# HBridge.net
KiCad netlist of a schematic drawn in EAGLE
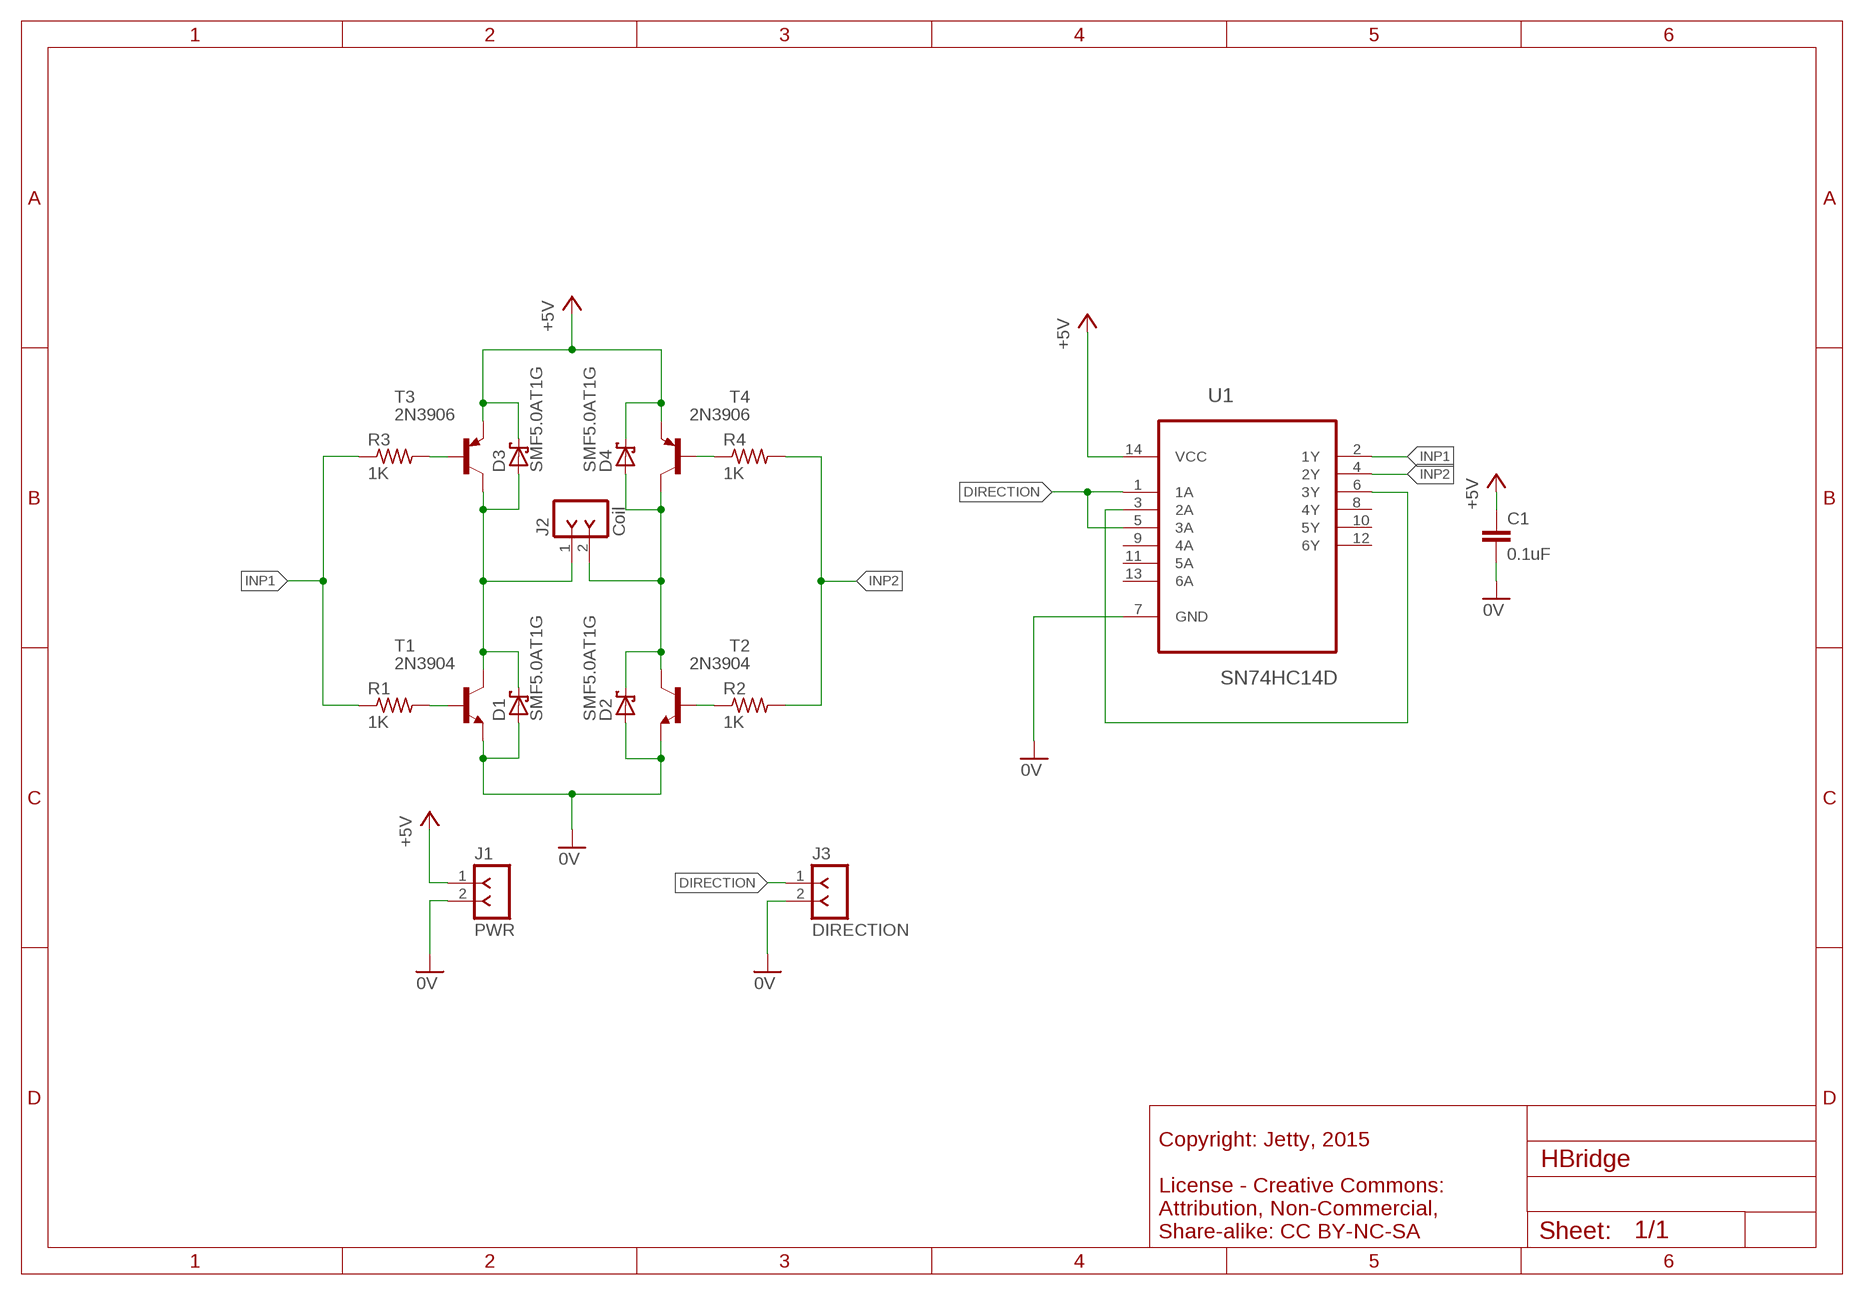
[diagram p0: schematic, sheet 1]

(export (version "E")
  (design (tool "Eeschema 10.0.6"))
  (components
    (comp (ref "C1")
      (value "0.1uF")
      (footprint "eagle-import:C0603")
      (libsource (lib "eagle-import") (part "C-EUC0603"))
    )
    (comp (ref "D1")
      (value "SMF5.0AT1G")
      (footprint "eagle-import:SOD123FL")
      (libsource (lib "eagle-import") (part "SMF5.0AT1"))
    )
    (comp (ref "D2")
      (value "SMF5.0AT1G")
      (footprint "eagle-import:SOD123FL")
      (libsource (lib "eagle-import") (part "SMF5.0AT1"))
    )
    (comp (ref "D3")
      (value "SMF5.0AT1G")
      (footprint "eagle-import:SOD123FL")
      (libsource (lib "eagle-import") (part "SMF5.0AT1"))
    )
    (comp (ref "D4")
      (value "SMF5.0AT1G")
      (footprint "eagle-import:SOD123FL")
      (libsource (lib "eagle-import") (part "SMF5.0AT1"))
    )
    (comp (ref "J1")
      (value "PWR")
      (footprint "eagle-import:SIP-100-02-32Y")
      (libsource (lib "eagle-import") (part "F-1X02-SIP-100-32Y"))
    )
    (comp (ref "J2")
      (value "Coil")
      (footprint "eagle-import:SIP-100-02-32Y")
      (libsource (lib "eagle-import") (part "F-1X02-SIP-100-32Y"))
    )
    (comp (ref "J3")
      (value "DIRECTION")
      (footprint "eagle-import:SIP-100-02-32Y")
      (libsource (lib "eagle-import") (part "F-1X02-SIP-100-32Y"))
    )
    (comp (ref "R1")
      (value "1K")
      (footprint "eagle-import:R0603")
      (libsource (lib "eagle-import") (part "R-US_R0603"))
    )
    (comp (ref "R2")
      (value "1K")
      (footprint "eagle-import:R0603")
      (libsource (lib "eagle-import") (part "R-US_R0603"))
    )
    (comp (ref "R3")
      (value "1K")
      (footprint "eagle-import:R0603")
      (libsource (lib "eagle-import") (part "R-US_R0603"))
    )
    (comp (ref "R4")
      (value "1K")
      (footprint "eagle-import:R0603")
      (libsource (lib "eagle-import") (part "R-US_R0603"))
    )
    (comp (ref "T1")
      (value "2N3904")
      (footprint "eagle-import:SOT23-BEC")
      (libsource (lib "eagle-import") (part "-NPN-SOT23-BECMMBT3904LT1"))
    )
    (comp (ref "T2")
      (value "2N3904")
      (footprint "eagle-import:SOT23-BEC")
      (libsource (lib "eagle-import") (part "-NPN-SOT23-BECMMBT3904LT1"))
    )
    (comp (ref "T3")
      (value "2N3906")
      (footprint "eagle-import:SOT23-BEC")
      (libsource (lib "eagle-import") (part "-PNP-SOT23-BECMMBT3906LT1"))
    )
    (comp (ref "T4")
      (value "2N3906")
      (footprint "eagle-import:SOT23-BEC")
      (libsource (lib "eagle-import") (part "-PNP-SOT23-BECMMBT3906LT1"))
    )
    (comp (ref "U1")
      (value "SN74HC14D")
      (footprint "eagle-import:SOIC127P600X175-14N")
      (libsource (lib "eagle-import") (part "SN74HC14D"))
    )
  )
  (nets
    (net (code "1") (name "+5V") (class "Default")
      (node (ref "C1") (pin "1") (pinfunction "1_1") (pintype "passive"))
      (node (ref "D3") (pin "C") (pinfunction "C_C") (pintype "passive"))
      (node (ref "D4") (pin "C") (pinfunction "C_C") (pintype "passive"))
      (node (ref "J1") (pin "1") (pinfunction "1_1") (pintype "passive"))
      (node (ref "T3") (pin "E") (pinfunction "E_E") (pintype "passive"))
      (node (ref "T4") (pin "E") (pinfunction "E_E") (pintype "passive"))
      (node (ref "U1") (pin "14") (pinfunction "VCC_14") (pintype "power_in"))
    )
    (net (code "2") (name "0V") (class "Default")
      (node (ref "C1") (pin "2") (pinfunction "2_2") (pintype "passive"))
      (node (ref "D1") (pin "A") (pinfunction "A_A") (pintype "passive"))
      (node (ref "D2") (pin "A") (pinfunction "A_A") (pintype "passive"))
      (node (ref "J1") (pin "2") (pinfunction "2_2") (pintype "passive"))
      (node (ref "J3") (pin "2") (pinfunction "2_2") (pintype "passive"))
      (node (ref "T1") (pin "E") (pinfunction "E_E") (pintype "passive"))
      (node (ref "T2") (pin "E") (pinfunction "E_E") (pintype "passive"))
      (node (ref "U1") (pin "7") (pinfunction "GND_7") (pintype "passive"))
    )
    (net (code "3") (name "DIRECTION") (class "Default")
      (node (ref "J3") (pin "1") (pinfunction "1_1") (pintype "passive"))
      (node (ref "U1") (pin "1") (pinfunction "1A_1") (pintype "input"))
      (node (ref "U1") (pin "5") (pinfunction "3A_5") (pintype "input"))
    )
    (net (code "4") (name "INP1") (class "Default")
      (node (ref "R1") (pin "1") (pinfunction "1_1") (pintype "passive"))
      (node (ref "R3") (pin "1") (pinfunction "1_1") (pintype "passive"))
      (node (ref "U1") (pin "2") (pinfunction "1Y_2") (pintype "output"))
    )
    (net (code "5") (name "INP2") (class "Default")
      (node (ref "R2") (pin "2") (pinfunction "2_2") (pintype "passive"))
      (node (ref "R4") (pin "2") (pinfunction "2_2") (pintype "passive"))
      (node (ref "U1") (pin "4") (pinfunction "2Y_4") (pintype "output"))
    )
    (net (code "6") (name "Net-(D1-PadC)") (class "Default")
      (node (ref "D1") (pin "C") (pinfunction "C_C") (pintype "passive"))
      (node (ref "D3") (pin "A") (pinfunction "A_A") (pintype "passive"))
      (node (ref "J2") (pin "1") (pinfunction "1_1") (pintype "passive"))
      (node (ref "T1") (pin "C") (pinfunction "C_C") (pintype "passive"))
      (node (ref "T3") (pin "C") (pinfunction "C_C") (pintype "passive"))
    )
    (net (code "7") (name "Net-(D2-PadC)") (class "Default")
      (node (ref "D2") (pin "C") (pinfunction "C_C") (pintype "passive"))
      (node (ref "D4") (pin "A") (pinfunction "A_A") (pintype "passive"))
      (node (ref "J2") (pin "2") (pinfunction "2_2") (pintype "passive"))
      (node (ref "T2") (pin "C") (pinfunction "C_C") (pintype "passive"))
      (node (ref "T4") (pin "C") (pinfunction "C_C") (pintype "passive"))
    )
    (net (code "8") (name "Net-(R1-Pad2)") (class "Default")
      (node (ref "R1") (pin "2") (pinfunction "2_2") (pintype "passive"))
      (node (ref "T1") (pin "B") (pinfunction "B_B") (pintype "passive"))
    )
    (net (code "9") (name "Net-(R2-Pad1)") (class "Default")
      (node (ref "R2") (pin "1") (pinfunction "1_1") (pintype "passive"))
      (node (ref "T2") (pin "B") (pinfunction "B_B") (pintype "passive"))
    )
    (net (code "10") (name "Net-(R3-Pad2)") (class "Default")
      (node (ref "R3") (pin "2") (pinfunction "2_2") (pintype "passive"))
      (node (ref "T3") (pin "B") (pinfunction "B_B") (pintype "passive"))
    )
    (net (code "11") (name "Net-(R4-Pad1)") (class "Default")
      (node (ref "R4") (pin "1") (pinfunction "1_1") (pintype "passive"))
      (node (ref "T4") (pin "B") (pinfunction "B_B") (pintype "passive"))
    )
    (net (code "12") (name "Net-(U1-2A)") (class "Default")
      (node (ref "U1") (pin "3") (pinfunction "2A_3") (pintype "input"))
      (node (ref "U1") (pin "6") (pinfunction "3Y_6") (pintype "output"))
    )
    (net (code "13") (name "unconnected-(U1-4A-Pad9)") (class "Default")
      (node (ref "U1") (pin "9") (pinfunction "4A_9") (pintype "input"))
    )
    (net (code "14") (name "unconnected-(U1-4Y-Pad8)") (class "Default")
      (node (ref "U1") (pin "8") (pinfunction "4Y_8") (pintype "output"))
    )
    (net (code "15") (name "unconnected-(U1-5A-Pad11)") (class "Default")
      (node (ref "U1") (pin "11") (pinfunction "5A_11") (pintype "input"))
    )
    (net (code "16") (name "unconnected-(U1-5Y-Pad10)") (class "Default")
      (node (ref "U1") (pin "10") (pinfunction "5Y_10") (pintype "output"))
    )
    (net (code "17") (name "unconnected-(U1-6A-Pad13)") (class "Default")
      (node (ref "U1") (pin "13") (pinfunction "6A_13") (pintype "input"))
    )
    (net (code "18") (name "unconnected-(U1-6Y-Pad12)") (class "Default")
      (node (ref "U1") (pin "12") (pinfunction "6Y_12") (pintype "output"))
    )
  )
)
